# 22257_v8.net
KiCad netlist of a schematic drawn in EAGLE
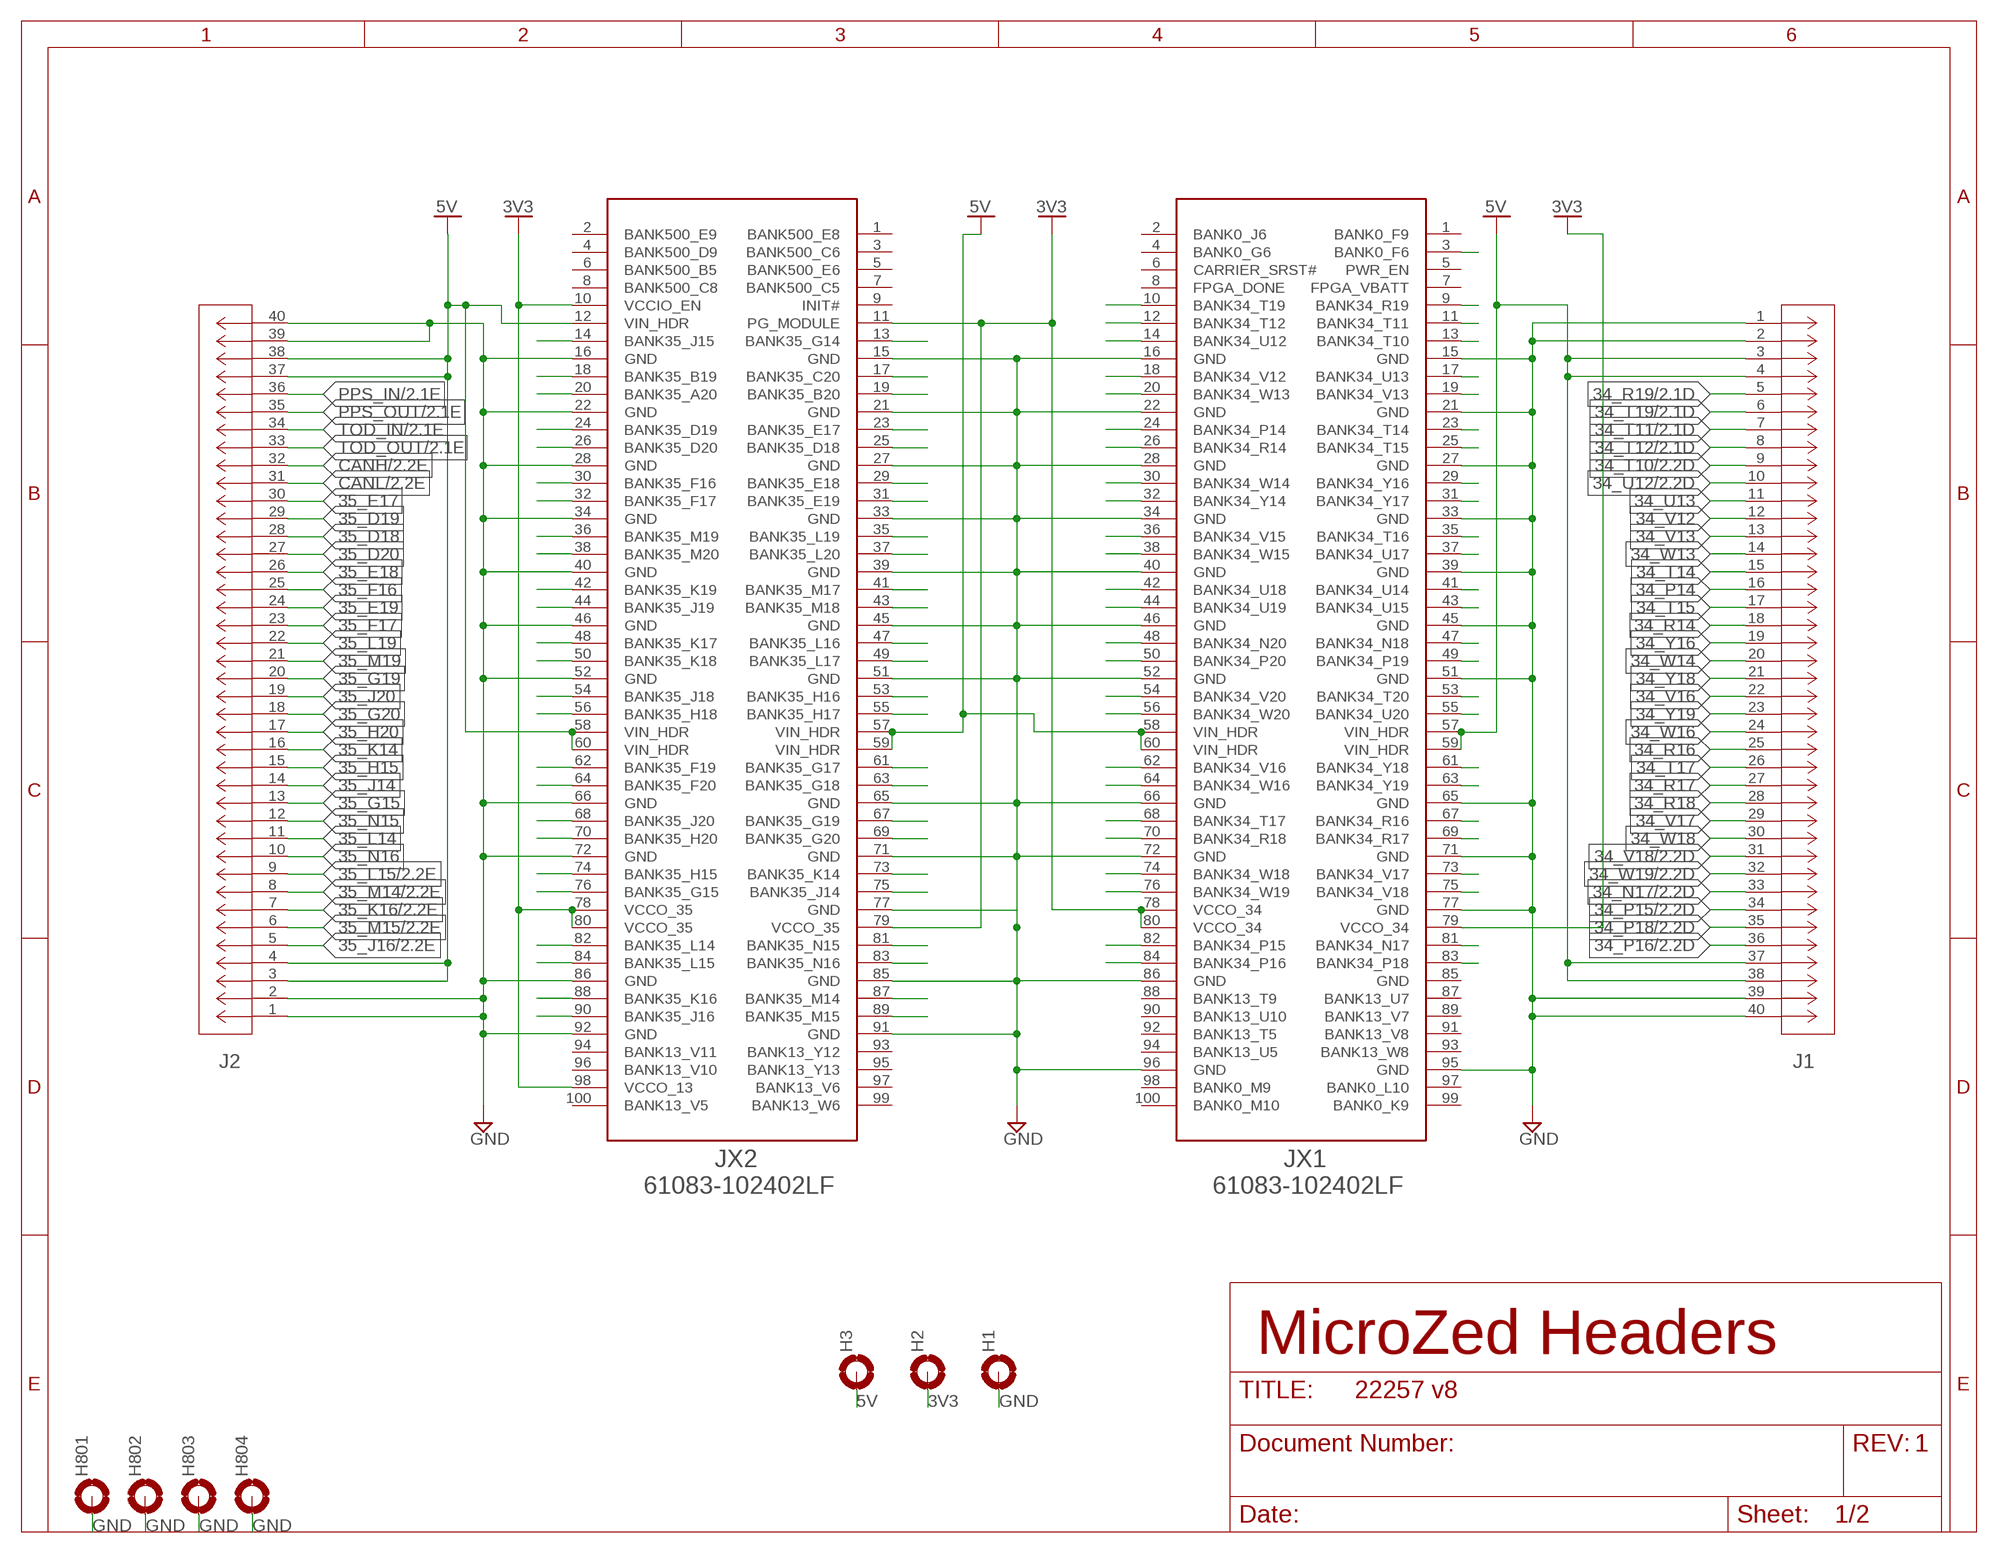
[diagram p0: schematic, sheet 1]
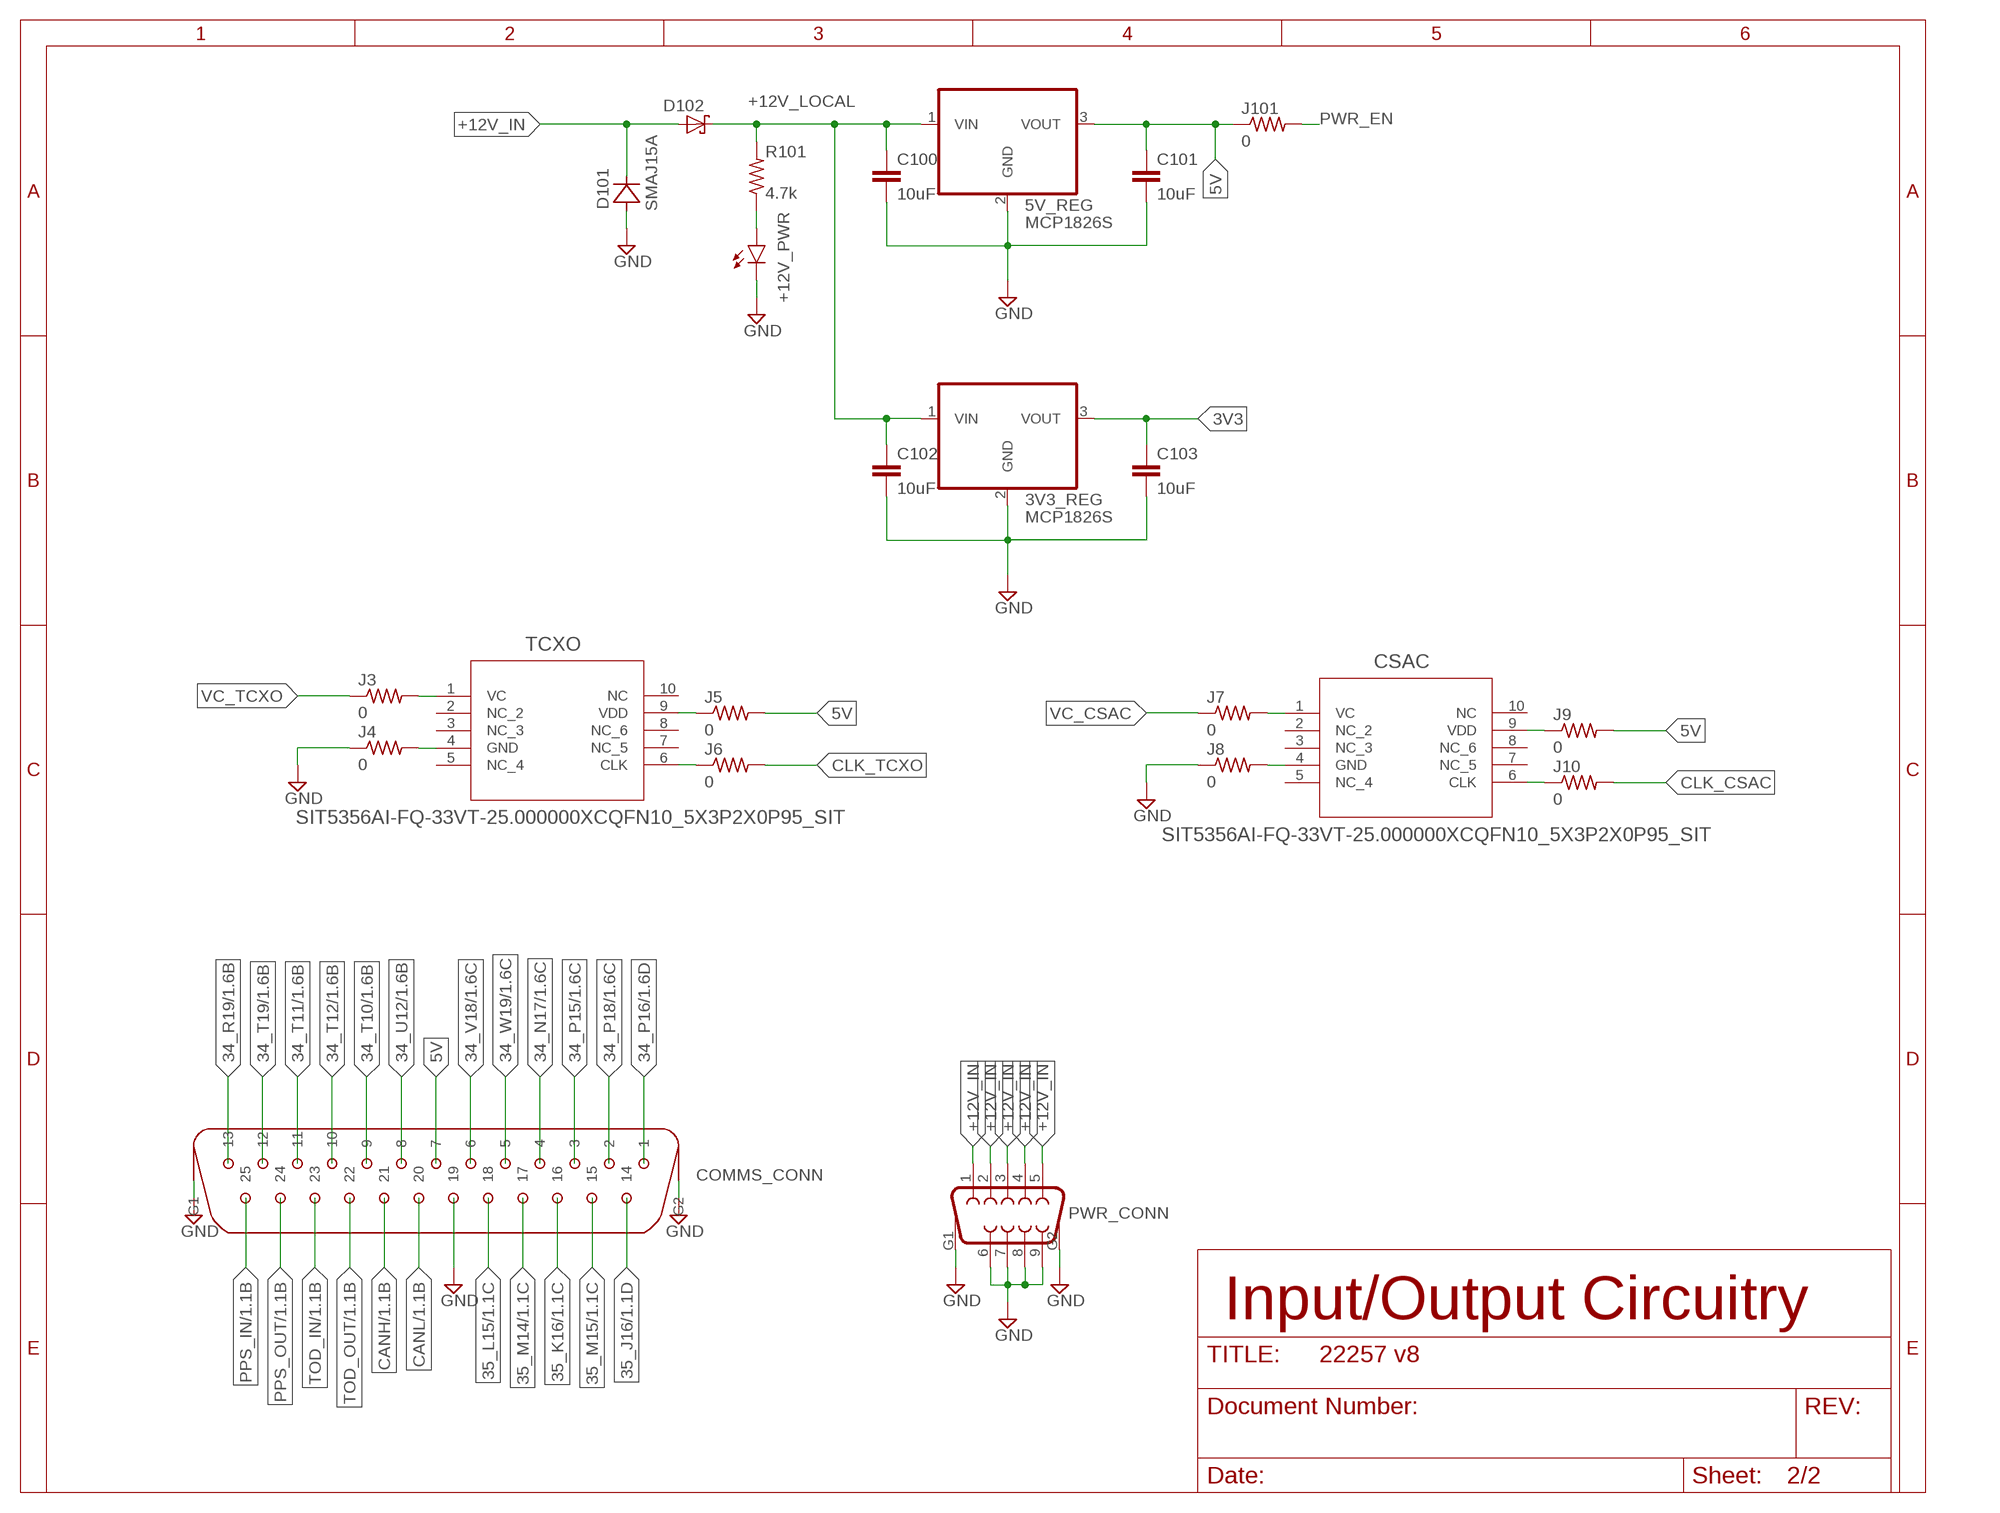
[diagram p1: schematic, sheet 2]

(export (version "E")
  (design (tool "Eeschema 10.0.6"))
  (components
    (comp (ref "H1")
      (value "MOUNT-PAD-ROUND5.0")
      (footprint "eagle-import:5,0-PAD")
      (libsource (lib "eagle-import") (part "MOUNT-PAD-ROUND5.0"))
    )
    (comp (ref "H2")
      (value "MOUNT-PAD-ROUND5.0")
      (footprint "eagle-import:5,0-PAD")
      (libsource (lib "eagle-import") (part "MOUNT-PAD-ROUND5.0"))
    )
    (comp (ref "H3")
      (value "MOUNT-PAD-ROUND5.0")
      (footprint "eagle-import:5,0-PAD")
      (libsource (lib "eagle-import") (part "MOUNT-PAD-ROUND5.0"))
    )
    (comp (ref "H801")
      (value "MOUNT-PAD-ROUND5.0")
      (footprint "eagle-import:5,0-PAD")
      (libsource (lib "eagle-import") (part "MOUNT-PAD-ROUND5.0"))
    )
    (comp (ref "H802")
      (value "MOUNT-PAD-ROUND5.0")
      (footprint "eagle-import:5,0-PAD")
      (libsource (lib "eagle-import") (part "MOUNT-PAD-ROUND5.0"))
    )
    (comp (ref "H803")
      (value "MOUNT-PAD-ROUND5.0")
      (footprint "eagle-import:5,0-PAD")
      (libsource (lib "eagle-import") (part "MOUNT-PAD-ROUND5.0"))
    )
    (comp (ref "H804")
      (value "MOUNT-PAD-ROUND5.0")
      (footprint "eagle-import:5,0-PAD")
      (libsource (lib "eagle-import") (part "MOUNT-PAD-ROUND5.0"))
    )
    (comp (ref "J1")
      (value "TD-120-G-AACON40_2X20_TU_HTS_SAI")
      (footprint "eagle-import:CON40_2X20_TU_HTS_SAI")
      (fields
        (field (name "MANUFACTURER_PART_NUMBER") "TD-120-G-AA")
        (field (name "COPYRIGHT") "Copyright (C) 2024 Ultra Librarian. All rights reserved.")
      )
      (libsource (lib "eagle-import") (part "TD-120-G-AACON40_2X20_TU_HTS_SAI"))
    )
    (comp (ref "J2")
      (value "TD-120-G-AACON40_2X20_TU_HTS_SAI")
      (footprint "eagle-import:CON40_2X20_TU_HTS_SAI")
      (fields
        (field (name "MANUFACTURER_PART_NUMBER") "TD-120-G-AA")
        (field (name "COPYRIGHT") "Copyright (C) 2024 Ultra Librarian. All rights reserved.")
      )
      (libsource (lib "eagle-import") (part "TD-120-G-AACON40_2X20_TU_HTS_SAI"))
    )
    (comp (ref "JX1")
      (value "61083-102402LF")
      (footprint "eagle-import:61083-102402LF")
      (libsource (lib "eagle-import") (part "61083-102402LF-JX1"))
    )
    (comp (ref "JX2")
      (value "61083-102402LF")
      (footprint "eagle-import:61083-102402LF")
      (libsource (lib "eagle-import") (part "61083-102402LF-JX2"))
    )
    (comp (ref "+12V_PWR")
      (value "LEDCHIP-LED0603")
      (footprint "eagle-import:CHIP-LED0603")
      (libsource (lib "eagle-import") (part "LEDCHIP-LED0603"))
    )
    (comp (ref "3V3_REG")
      (value "MCP1826S")
      (footprint "eagle-import:TO220-3")
      (libsource (lib "eagle-import") (part "MCP1826S"))
    )
    (comp (ref "5V_REG")
      (value "MCP1826S")
      (footprint "eagle-import:TO220-3")
      (libsource (lib "eagle-import") (part "MCP1826S"))
    )
    (comp (ref "C100")
      (value "10uF")
      (footprint "eagle-import:C0805")
      (libsource (lib "eagle-import") (part "C-EUC0805"))
    )
    (comp (ref "C101")
      (value "10uF")
      (footprint "eagle-import:C0805")
      (libsource (lib "eagle-import") (part "C-EUC0805"))
    )
    (comp (ref "C102")
      (value "10uF")
      (footprint "eagle-import:C0805")
      (libsource (lib "eagle-import") (part "C-EUC0805"))
    )
    (comp (ref "C103")
      (value "10uF")
      (footprint "eagle-import:C0805")
      (libsource (lib "eagle-import") (part "C-EUC0805"))
    )
    (comp (ref "COMMS_CONN")
      (value "M25HP")
      (footprint "eagle-import:M25HP")
      (libsource (lib "eagle-import") (part "M25HP"))
    )
    (comp (ref "CSAC")
      (value "SIT5356AI-FQ-33VT-25.000000XCQFN10_5X3P2X0P95_SIT")
      (footprint "eagle-import:CQFN10_5X3P2X0P95_SIT")
      (fields
        (field (name "MANUFACTURER_PART_NUMBER") "SIT5356AI-FQ-33VT-25.000000X")
        (field (name "COPYRIGHT") "Copyright (C) 2024 Ultra Librarian. All rights reserved.")
      )
      (libsource (lib "eagle-import") (part "SIT5356AI-FQ-33VT-25.000000XCQFN10_5X3P2X0P95_SIT"))
    )
    (comp (ref "D101")
      (value "SMAJ15A")
      (footprint "eagle-import:SMA")
      (libsource (lib "eagle-import") (part "MBRA340T3"))
    )
    (comp (ref "D102")
      (value "SCHOTTKY-DIODESMC")
      (footprint "eagle-import:SMC")
      (libsource (lib "eagle-import") (part "SCHOTTKY-DIODESMC"))
    )
    (comp (ref "J3")
      (value "0")
      (footprint "eagle-import:R0603")
      (libsource (lib "eagle-import") (part "R-US_R0603"))
    )
    (comp (ref "J4")
      (value "0")
      (footprint "eagle-import:R0603")
      (libsource (lib "eagle-import") (part "R-US_R0603"))
    )
    (comp (ref "J5")
      (value "0")
      (footprint "eagle-import:R0603")
      (libsource (lib "eagle-import") (part "R-US_R0603"))
    )
    (comp (ref "J6")
      (value "0")
      (footprint "eagle-import:R0603")
      (libsource (lib "eagle-import") (part "R-US_R0603"))
    )
    (comp (ref "J7")
      (value "0")
      (footprint "eagle-import:R0603")
      (libsource (lib "eagle-import") (part "R-US_R0603"))
    )
    (comp (ref "J8")
      (value "0")
      (footprint "eagle-import:R0603")
      (libsource (lib "eagle-import") (part "R-US_R0603"))
    )
    (comp (ref "J9")
      (value "0")
      (footprint "eagle-import:R0603")
      (libsource (lib "eagle-import") (part "R-US_R0603"))
    )
    (comp (ref "J10")
      (value "0")
      (footprint "eagle-import:R0603")
      (libsource (lib "eagle-import") (part "R-US_R0603"))
    )
    (comp (ref "J101")
      (value "0")
      (footprint "eagle-import:R0603")
      (libsource (lib "eagle-import") (part "R-US_R0603"))
    )
    (comp (ref "PWR_CONN")
      (value "DSUB9PIN")
      (footprint "eagle-import:DSUB9HP")
      (libsource (lib "eagle-import") (part "DSUB9PIN"))
    )
    (comp (ref "R101")
      (value "4.7k")
      (footprint "eagle-import:R0603")
      (libsource (lib "eagle-import") (part "R-US_R0603"))
    )
    (comp (ref "TCXO")
      (value "SIT5356AI-FQ-33VT-25.000000XCQFN10_5X3P2X0P95_SIT")
      (footprint "eagle-import:CQFN10_5X3P2X0P95_SIT")
      (fields
        (field (name "MANUFACTURER_PART_NUMBER") "SIT5356AI-FQ-33VT-25.000000X")
        (field (name "COPYRIGHT") "Copyright (C) 2024 Ultra Librarian. All rights reserved.")
      )
      (libsource (lib "eagle-import") (part "SIT5356AI-FQ-33VT-25.000000XCQFN10_5X3P2X0P95_SIT"))
    )
  )
  (nets
    (net (code "1") (name "+12V_IN") (class "Default")
      (node (ref "D101") (pin "C") (pinfunction "C_C") (pintype "passive"))
      (node (ref "D102") (pin "A") (pinfunction "A_A") (pintype "passive"))
      (node (ref "PWR_CONN") (pin "1") (pinfunction "1_1") (pintype "passive"))
      (node (ref "PWR_CONN") (pin "2") (pinfunction "2_2") (pintype "passive"))
      (node (ref "PWR_CONN") (pin "3") (pinfunction "3_3") (pintype "passive"))
      (node (ref "PWR_CONN") (pin "4") (pinfunction "4_4") (pintype "passive"))
      (node (ref "PWR_CONN") (pin "5") (pinfunction "5_5") (pintype "passive"))
    )
    (net (code "2") (name "+12V_LOCAL") (class "Default")
      (node (ref "3V3_REG") (pin "1") (pinfunction "VIN_1") (pintype "input"))
      (node (ref "5V_REG") (pin "1") (pinfunction "VIN_1") (pintype "input"))
      (node (ref "C100") (pin "1") (pinfunction "1_1") (pintype "passive"))
      (node (ref "C102") (pin "1") (pinfunction "1_1") (pintype "passive"))
      (node (ref "D102") (pin "C") (pinfunction "C_C") (pintype "passive"))
      (node (ref "R101") (pin "2") (pinfunction "2_2") (pintype "passive"))
    )
    (net (code "3") (name "3V3") (class "Default")
      (node (ref "3V3_REG") (pin "3") (pinfunction "VOUT_3") (pintype "passive"))
      (node (ref "C103") (pin "1") (pinfunction "1_1") (pintype "passive"))
      (node (ref "H2") (pin "B5") (pinfunction "MOUNT_B5") (pintype "passive"))
      (node (ref "JX1") (pin "78") (pinfunction "VCCO_34_78") (pintype "bidirectional"))
      (node (ref "JX1") (pin "79") (pinfunction "VCCO_34_79") (pintype "bidirectional"))
      (node (ref "JX1") (pin "80") (pinfunction "VCCO_34_80") (pintype "bidirectional"))
      (node (ref "JX2") (pin "10") (pinfunction "VCCIO_EN_10") (pintype "bidirectional"))
      (node (ref "JX2") (pin "11") (pinfunction "PG_MODULE_11") (pintype "bidirectional"))
      (node (ref "JX2") (pin "78") (pinfunction "VCCO_35_78") (pintype "bidirectional"))
      (node (ref "JX2") (pin "79") (pinfunction "VCCO_35_79") (pintype "bidirectional"))
      (node (ref "JX2") (pin "80") (pinfunction "VCCO_35_80") (pintype "bidirectional"))
      (node (ref "JX2") (pin "98") (pinfunction "VCCO_13_98") (pintype "bidirectional"))
    )
    (net (code "4") (name "5V") (class "Default")
      (node (ref "5V_REG") (pin "3") (pinfunction "VOUT_3") (pintype "passive"))
      (node (ref "C101") (pin "1") (pinfunction "1_1") (pintype "passive"))
      (node (ref "COMMS_CONN") (pin "7") (pinfunction "7_7") (pintype "bidirectional"))
      (node (ref "H3") (pin "B5") (pinfunction "MOUNT_B5") (pintype "passive"))
      (node (ref "J1") (pin "3") (pinfunction "3_3") (pintype "passive"))
      (node (ref "J1") (pin "37") (pinfunction "37_37") (pintype "passive"))
      (node (ref "J1") (pin "38") (pinfunction "38_38") (pintype "passive"))
      (node (ref "J1") (pin "4") (pinfunction "4_4") (pintype "passive"))
      (node (ref "J101") (pin "1") (pinfunction "1_1") (pintype "passive"))
      (node (ref "J2") (pin "3") (pinfunction "3_3") (pintype "passive"))
      (node (ref "J2") (pin "37") (pinfunction "37_37") (pintype "passive"))
      (node (ref "J2") (pin "38") (pinfunction "38_38") (pintype "passive"))
      (node (ref "J2") (pin "4") (pinfunction "4_4") (pintype "passive"))
      (node (ref "J5") (pin "2") (pinfunction "2_2") (pintype "passive"))
      (node (ref "J9") (pin "2") (pinfunction "2_2") (pintype "passive"))
      (node (ref "JX1") (pin "57") (pinfunction "VIN_HDR_57") (pintype "bidirectional"))
      (node (ref "JX1") (pin "58") (pinfunction "VIN_HDR_58") (pintype "bidirectional"))
      (node (ref "JX1") (pin "59") (pinfunction "VIN_HDR_59") (pintype "bidirectional"))
      (node (ref "JX1") (pin "60") (pinfunction "VIN_HDR_60") (pintype "bidirectional"))
      (node (ref "JX2") (pin "12") (pinfunction "VIN_HDR_12") (pintype "bidirectional"))
      (node (ref "JX2") (pin "57") (pinfunction "VIN_HDR_57") (pintype "bidirectional"))
      (node (ref "JX2") (pin "58") (pinfunction "VIN_HDR_58") (pintype "bidirectional"))
      (node (ref "JX2") (pin "59") (pinfunction "VIN_HDR_59") (pintype "bidirectional"))
      (node (ref "JX2") (pin "60") (pinfunction "VIN_HDR_60") (pintype "bidirectional"))
    )
    (net (code "5") (name "34_N17") (class "Default")
      (node (ref "COMMS_CONN") (pin "4") (pinfunction "4_4") (pintype "bidirectional"))
      (node (ref "J1") (pin "33") (pinfunction "33_33") (pintype "passive"))
      (node (ref "JX1") (pin "81") (pinfunction "BANK34_N17_81") (pintype "bidirectional"))
    )
    (net (code "6") (name "34_P14") (class "Default")
      (node (ref "J1") (pin "16") (pinfunction "16_16") (pintype "passive"))
      (node (ref "JX1") (pin "24") (pinfunction "BANK34_P14_24") (pintype "bidirectional"))
    )
    (net (code "7") (name "34_P15") (class "Default")
      (node (ref "COMMS_CONN") (pin "3") (pinfunction "3_3") (pintype "bidirectional"))
      (node (ref "J1") (pin "34") (pinfunction "34_34") (pintype "passive"))
      (node (ref "JX1") (pin "82") (pinfunction "BANK34_P15_82") (pintype "bidirectional"))
    )
    (net (code "8") (name "34_P16") (class "Default")
      (node (ref "COMMS_CONN") (pin "1") (pinfunction "1_1") (pintype "bidirectional"))
      (node (ref "J1") (pin "36") (pinfunction "36_36") (pintype "passive"))
      (node (ref "JX1") (pin "84") (pinfunction "BANK34_P16_84") (pintype "bidirectional"))
    )
    (net (code "9") (name "34_P18") (class "Default")
      (node (ref "COMMS_CONN") (pin "2") (pinfunction "2_2") (pintype "bidirectional"))
      (node (ref "J1") (pin "35") (pinfunction "35_35") (pintype "passive"))
      (node (ref "JX1") (pin "83") (pinfunction "BANK34_P18_83") (pintype "bidirectional"))
    )
    (net (code "10") (name "34_R14") (class "Default")
      (node (ref "J1") (pin "18") (pinfunction "18_18") (pintype "passive"))
      (node (ref "JX1") (pin "26") (pinfunction "BANK34_R14_26") (pintype "bidirectional"))
    )
    (net (code "11") (name "34_R16") (class "Default")
      (node (ref "J1") (pin "25") (pinfunction "25_25") (pintype "passive"))
      (node (ref "JX1") (pin "67") (pinfunction "BANK34_R16_67") (pintype "bidirectional"))
    )
    (net (code "12") (name "34_R17") (class "Default")
      (node (ref "J1") (pin "27") (pinfunction "27_27") (pintype "passive"))
      (node (ref "JX1") (pin "69") (pinfunction "BANK34_R17_69") (pintype "bidirectional"))
    )
    (net (code "13") (name "34_R18") (class "Default")
      (node (ref "J1") (pin "28") (pinfunction "28_28") (pintype "passive"))
      (node (ref "JX1") (pin "70") (pinfunction "BANK34_R18_70") (pintype "bidirectional"))
    )
    (net (code "14") (name "34_R19") (class "Default")
      (node (ref "COMMS_CONN") (pin "13") (pinfunction "13_13") (pintype "bidirectional"))
      (node (ref "J1") (pin "5") (pinfunction "5_5") (pintype "passive"))
      (node (ref "JX1") (pin "9") (pinfunction "BANK34_R19_9") (pintype "bidirectional"))
    )
    (net (code "15") (name "34_T10") (class "Default")
      (node (ref "COMMS_CONN") (pin "9") (pinfunction "9_9") (pintype "bidirectional"))
      (node (ref "J1") (pin "9") (pinfunction "9_9") (pintype "passive"))
      (node (ref "JX1") (pin "13") (pinfunction "BANK34_T10_13") (pintype "bidirectional"))
    )
    (net (code "16") (name "34_T11") (class "Default")
      (node (ref "COMMS_CONN") (pin "11") (pinfunction "11_11") (pintype "bidirectional"))
      (node (ref "J1") (pin "7") (pinfunction "7_7") (pintype "passive"))
      (node (ref "JX1") (pin "11") (pinfunction "BANK34_T11_11") (pintype "bidirectional"))
    )
    (net (code "17") (name "34_T12") (class "Default")
      (node (ref "COMMS_CONN") (pin "10") (pinfunction "10_10") (pintype "bidirectional"))
      (node (ref "J1") (pin "8") (pinfunction "8_8") (pintype "passive"))
      (node (ref "JX1") (pin "12") (pinfunction "BANK34_T12_12") (pintype "bidirectional"))
    )
    (net (code "18") (name "34_T14") (class "Default")
      (node (ref "J1") (pin "15") (pinfunction "15_15") (pintype "passive"))
      (node (ref "JX1") (pin "23") (pinfunction "BANK34_T14_23") (pintype "bidirectional"))
    )
    (net (code "19") (name "34_T15") (class "Default")
      (node (ref "J1") (pin "17") (pinfunction "17_17") (pintype "passive"))
      (node (ref "JX1") (pin "25") (pinfunction "BANK34_T15_25") (pintype "bidirectional"))
    )
    (net (code "20") (name "34_T17") (class "Default")
      (node (ref "J1") (pin "26") (pinfunction "26_26") (pintype "passive"))
      (node (ref "JX1") (pin "68") (pinfunction "BANK34_T17_68") (pintype "bidirectional"))
    )
    (net (code "21") (name "34_T19") (class "Default")
      (node (ref "COMMS_CONN") (pin "12") (pinfunction "12_12") (pintype "bidirectional"))
      (node (ref "J1") (pin "6") (pinfunction "6_6") (pintype "passive"))
      (node (ref "JX1") (pin "10") (pinfunction "BANK34_T19_10") (pintype "bidirectional"))
    )
    (net (code "22") (name "34_U12") (class "Default")
      (node (ref "COMMS_CONN") (pin "8") (pinfunction "8_8") (pintype "bidirectional"))
      (node (ref "J1") (pin "10") (pinfunction "10_10") (pintype "passive"))
      (node (ref "JX1") (pin "14") (pinfunction "BANK34_U12_14") (pintype "bidirectional"))
    )
    (net (code "23") (name "34_U13") (class "Default")
      (node (ref "J1") (pin "11") (pinfunction "11_11") (pintype "passive"))
      (node (ref "JX1") (pin "17") (pinfunction "BANK34_U13_17") (pintype "bidirectional"))
    )
    (net (code "24") (name "34_V12") (class "Default")
      (node (ref "J1") (pin "12") (pinfunction "12_12") (pintype "passive"))
      (node (ref "JX1") (pin "18") (pinfunction "BANK34_V12_18") (pintype "bidirectional"))
    )
    (net (code "25") (name "34_V13") (class "Default")
      (node (ref "J1") (pin "13") (pinfunction "13_13") (pintype "passive"))
      (node (ref "JX1") (pin "19") (pinfunction "BANK34_V13_19") (pintype "bidirectional"))
    )
    (net (code "26") (name "34_V16") (class "Default")
      (node (ref "J1") (pin "22") (pinfunction "22_22") (pintype "passive"))
      (node (ref "JX1") (pin "62") (pinfunction "BANK34_V16_62") (pintype "bidirectional"))
    )
    (net (code "27") (name "34_V17") (class "Default")
      (node (ref "J1") (pin "29") (pinfunction "29_29") (pintype "passive"))
      (node (ref "JX1") (pin "73") (pinfunction "BANK34_V17_73") (pintype "bidirectional"))
    )
    (net (code "28") (name "34_V18") (class "Default")
      (node (ref "COMMS_CONN") (pin "6") (pinfunction "6_6") (pintype "bidirectional"))
      (node (ref "J1") (pin "31") (pinfunction "31_31") (pintype "passive"))
      (node (ref "JX1") (pin "75") (pinfunction "BANK34_V18_75") (pintype "bidirectional"))
    )
    (net (code "29") (name "34_W13") (class "Default")
      (node (ref "J1") (pin "14") (pinfunction "14_14") (pintype "passive"))
      (node (ref "JX1") (pin "20") (pinfunction "BANK34_W13_20") (pintype "bidirectional"))
    )
    (net (code "30") (name "34_W14") (class "Default")
      (node (ref "J1") (pin "20") (pinfunction "20_20") (pintype "passive"))
      (node (ref "JX1") (pin "30") (pinfunction "BANK34_W14_30") (pintype "bidirectional"))
    )
    (net (code "31") (name "34_W16") (class "Default")
      (node (ref "J1") (pin "24") (pinfunction "24_24") (pintype "passive"))
      (node (ref "JX1") (pin "64") (pinfunction "BANK34_W16_64") (pintype "bidirectional"))
    )
    (net (code "32") (name "34_W18") (class "Default")
      (node (ref "J1") (pin "30") (pinfunction "30_30") (pintype "passive"))
      (node (ref "JX1") (pin "74") (pinfunction "BANK34_W18_74") (pintype "bidirectional"))
    )
    (net (code "33") (name "34_W19") (class "Default")
      (node (ref "COMMS_CONN") (pin "5") (pinfunction "5_5") (pintype "bidirectional"))
      (node (ref "J1") (pin "32") (pinfunction "32_32") (pintype "passive"))
      (node (ref "JX1") (pin "76") (pinfunction "BANK34_W19_76") (pintype "bidirectional"))
    )
    (net (code "34") (name "34_Y16") (class "Default")
      (node (ref "J1") (pin "19") (pinfunction "19_19") (pintype "passive"))
      (node (ref "JX1") (pin "29") (pinfunction "BANK34_Y16_29") (pintype "bidirectional"))
    )
    (net (code "35") (name "34_Y18") (class "Default")
      (node (ref "J1") (pin "21") (pinfunction "21_21") (pintype "passive"))
      (node (ref "JX1") (pin "61") (pinfunction "BANK34_Y18_61") (pintype "bidirectional"))
    )
    (net (code "36") (name "34_Y19") (class "Default")
      (node (ref "J1") (pin "23") (pinfunction "23_23") (pintype "passive"))
      (node (ref "JX1") (pin "63") (pinfunction "BANK34_Y19_63") (pintype "bidirectional"))
    )
    (net (code "37") (name "35_D18") (class "Default")
      (node (ref "J2") (pin "28") (pinfunction "28_28") (pintype "passive"))
      (node (ref "JX2") (pin "25") (pinfunction "BANK35_D18_25") (pintype "bidirectional"))
    )
    (net (code "38") (name "35_D19") (class "Default")
      (node (ref "J2") (pin "29") (pinfunction "29_29") (pintype "passive"))
      (node (ref "JX2") (pin "24") (pinfunction "BANK35_D19_24") (pintype "bidirectional"))
    )
    (net (code "39") (name "35_D20") (class "Default")
      (node (ref "J2") (pin "27") (pinfunction "27_27") (pintype "passive"))
      (node (ref "JX2") (pin "26") (pinfunction "BANK35_D20_26") (pintype "bidirectional"))
    )
    (net (code "40") (name "35_E17") (class "Default")
      (node (ref "J2") (pin "30") (pinfunction "30_30") (pintype "passive"))
      (node (ref "JX2") (pin "23") (pinfunction "BANK35_E17_23") (pintype "bidirectional"))
    )
    (net (code "41") (name "35_E18") (class "Default")
      (node (ref "J2") (pin "26") (pinfunction "26_26") (pintype "passive"))
      (node (ref "JX2") (pin "29") (pinfunction "BANK35_E18_29") (pintype "bidirectional"))
    )
    (net (code "42") (name "35_E19") (class "Default")
      (node (ref "J2") (pin "24") (pinfunction "24_24") (pintype "passive"))
      (node (ref "JX2") (pin "31") (pinfunction "BANK35_E19_31") (pintype "bidirectional"))
    )
    (net (code "43") (name "35_F16") (class "Default")
      (node (ref "J2") (pin "25") (pinfunction "25_25") (pintype "passive"))
      (node (ref "JX2") (pin "30") (pinfunction "BANK35_F16_30") (pintype "bidirectional"))
    )
    (net (code "44") (name "35_F17") (class "Default")
      (node (ref "J2") (pin "23") (pinfunction "23_23") (pintype "passive"))
      (node (ref "JX2") (pin "32") (pinfunction "BANK35_F17_32") (pintype "bidirectional"))
    )
    (net (code "45") (name "35_G15") (class "Default")
      (node (ref "J2") (pin "13") (pinfunction "13_13") (pintype "passive"))
      (node (ref "JX2") (pin "76") (pinfunction "BANK35_G15_76") (pintype "bidirectional"))
    )
    (net (code "46") (name "35_G19") (class "Default")
      (node (ref "J2") (pin "20") (pinfunction "20_20") (pintype "passive"))
      (node (ref "JX2") (pin "67") (pinfunction "BANK35_G19_67") (pintype "bidirectional"))
    )
    (net (code "47") (name "35_G20") (class "Default")
      (node (ref "J2") (pin "18") (pinfunction "18_18") (pintype "passive"))
      (node (ref "JX2") (pin "69") (pinfunction "BANK35_G20_69") (pintype "bidirectional"))
    )
    (net (code "48") (name "35_H15") (class "Default")
      (node (ref "J2") (pin "15") (pinfunction "15_15") (pintype "passive"))
      (node (ref "JX2") (pin "74") (pinfunction "BANK35_H15_74") (pintype "bidirectional"))
    )
    (net (code "49") (name "35_H20") (class "Default")
      (node (ref "J2") (pin "17") (pinfunction "17_17") (pintype "passive"))
      (node (ref "JX2") (pin "70") (pinfunction "BANK35_H20_70") (pintype "bidirectional"))
    )
    (net (code "50") (name "35_J14") (class "Default")
      (node (ref "J2") (pin "14") (pinfunction "14_14") (pintype "passive"))
      (node (ref "JX2") (pin "75") (pinfunction "BANK35_J14_75") (pintype "bidirectional"))
    )
    (net (code "51") (name "35_J16") (class "Default")
      (node (ref "COMMS_CONN") (pin "14") (pinfunction "14_14") (pintype "bidirectional"))
      (node (ref "J2") (pin "5") (pinfunction "5_5") (pintype "passive"))
      (node (ref "JX2") (pin "90") (pinfunction "BANK35_J16_90") (pintype "bidirectional"))
    )
    (net (code "52") (name "35_J20") (class "Default")
      (node (ref "J2") (pin "19") (pinfunction "19_19") (pintype "passive"))
      (node (ref "JX2") (pin "68") (pinfunction "BANK35_J20_68") (pintype "bidirectional"))
    )
    (net (code "53") (name "35_K14") (class "Default")
      (node (ref "J2") (pin "16") (pinfunction "16_16") (pintype "passive"))
      (node (ref "JX2") (pin "73") (pinfunction "BANK35_K14_73") (pintype "bidirectional"))
    )
    (net (code "54") (name "35_K16") (class "Default")
      (node (ref "COMMS_CONN") (pin "16") (pinfunction "16_16") (pintype "bidirectional"))
      (node (ref "J2") (pin "7") (pinfunction "7_7") (pintype "passive"))
      (node (ref "JX2") (pin "88") (pinfunction "BANK35_K16_88") (pintype "bidirectional"))
    )
    (net (code "55") (name "35_L14") (class "Default")
      (node (ref "J2") (pin "11") (pinfunction "11_11") (pintype "passive"))
      (node (ref "JX2") (pin "82") (pinfunction "BANK35_L14_82") (pintype "bidirectional"))
    )
    (net (code "56") (name "35_L15") (class "Default")
      (node (ref "COMMS_CONN") (pin "18") (pinfunction "18_18") (pintype "bidirectional"))
      (node (ref "J2") (pin "9") (pinfunction "9_9") (pintype "passive"))
      (node (ref "JX2") (pin "84") (pinfunction "BANK35_L15_84") (pintype "bidirectional"))
    )
    (net (code "57") (name "35_L19") (class "Default")
      (node (ref "J2") (pin "22") (pinfunction "22_22") (pintype "passive"))
      (node (ref "JX2") (pin "35") (pinfunction "BANK35_L19_35") (pintype "bidirectional"))
    )
    (net (code "58") (name "35_M14") (class "Default")
      (node (ref "COMMS_CONN") (pin "17") (pinfunction "17_17") (pintype "bidirectional"))
      (node (ref "J2") (pin "8") (pinfunction "8_8") (pintype "passive"))
      (node (ref "JX2") (pin "87") (pinfunction "BANK35_M14_87") (pintype "bidirectional"))
    )
    (net (code "59") (name "35_M15") (class "Default")
      (node (ref "COMMS_CONN") (pin "15") (pinfunction "15_15") (pintype "bidirectional"))
      (node (ref "J2") (pin "6") (pinfunction "6_6") (pintype "passive"))
      (node (ref "JX2") (pin "89") (pinfunction "BANK35_M15_89") (pintype "bidirectional"))
    )
    (net (code "60") (name "35_M19") (class "Default")
      (node (ref "J2") (pin "21") (pinfunction "21_21") (pintype "passive"))
      (node (ref "JX2") (pin "36") (pinfunction "BANK35_M19_36") (pintype "bidirectional"))
    )
    (net (code "61") (name "35_N15") (class "Default")
      (node (ref "J2") (pin "12") (pinfunction "12_12") (pintype "passive"))
      (node (ref "JX2") (pin "81") (pinfunction "BANK35_N15_81") (pintype "bidirectional"))
    )
    (net (code "62") (name "35_N16") (class "Default")
      (node (ref "J2") (pin "10") (pinfunction "10_10") (pintype "passive"))
      (node (ref "JX2") (pin "83") (pinfunction "BANK35_N16_83") (pintype "bidirectional"))
    )
    (net (code "63") (name "CANH") (class "Default")
      (node (ref "COMMS_CONN") (pin "21") (pinfunction "21_21") (pintype "bidirectional"))
      (node (ref "J2") (pin "32") (pinfunction "32_32") (pintype "passive"))
    )
    (net (code "64") (name "CANL") (class "Default")
      (node (ref "COMMS_CONN") (pin "20") (pinfunction "20_20") (pintype "bidirectional"))
      (node (ref "J2") (pin "31") (pinfunction "31_31") (pintype "passive"))
    )
    (net (code "65") (name "CLK_CSAC") (class "Default")
      (node (ref "J10") (pin "2") (pinfunction "2_2") (pintype "passive"))
    )
    (net (code "66") (name "CLK_TCXO") (class "Default")
      (node (ref "J6") (pin "2") (pinfunction "2_2") (pintype "passive"))
    )
    (net (code "67") (name "GND") (class "Default")
      (node (ref "+12V_PWR") (pin "C") (pinfunction "C_C") (pintype "passive"))
      (node (ref "3V3_REG") (pin "2") (pinfunction "GND_2") (pintype "input"))
      (node (ref "5V_REG") (pin "2") (pinfunction "GND_2") (pintype "input"))
      (node (ref "C100") (pin "2") (pinfunction "2_2") (pintype "passive"))
      (node (ref "C101") (pin "2") (pinfunction "2_2") (pintype "passive"))
      (node (ref "C102") (pin "2") (pinfunction "2_2") (pintype "passive"))
      (node (ref "C103") (pin "2") (pinfunction "2_2") (pintype "passive"))
      (node (ref "COMMS_CONN") (pin "19") (pinfunction "19_19") (pintype "bidirectional"))
      (node (ref "COMMS_CONN") (pin "G1") (pinfunction "G1_G1") (pintype "bidirectional"))
      (node (ref "COMMS_CONN") (pin "G2") (pinfunction "G2_G2") (pintype "bidirectional"))
      (node (ref "D101") (pin "A") (pinfunction "A_A") (pintype "passive"))
      (node (ref "H1") (pin "B5") (pinfunction "MOUNT_B5") (pintype "passive"))
      (node (ref "H801") (pin "B5") (pinfunction "MOUNT_B5") (pintype "passive"))
      (node (ref "H802") (pin "B5") (pinfunction "MOUNT_B5") (pintype "passive"))
      (node (ref "H803") (pin "B5") (pinfunction "MOUNT_B5") (pintype "passive"))
      (node (ref "H804") (pin "B5") (pinfunction "MOUNT_B5") (pintype "passive"))
      (node (ref "J1") (pin "1") (pinfunction "1_1") (pintype "passive"))
      (node (ref "J1") (pin "2") (pinfunction "2_2") (pintype "passive"))
      (node (ref "J1") (pin "39") (pinfunction "39_39") (pintype "passive"))
      (node (ref "J1") (pin "40") (pinfunction "40_40") (pintype "passive"))
      (node (ref "J2") (pin "1") (pinfunction "1_1") (pintype "passive"))
      (node (ref "J2") (pin "2") (pinfunction "2_2") (pintype "passive"))
      (node (ref "J2") (pin "39") (pinfunction "39_39") (pintype "passive"))
      (node (ref "J2") (pin "40") (pinfunction "40_40") (pintype "passive"))
      (node (ref "J4") (pin "1") (pinfunction "1_1") (pintype "passive"))
      (node (ref "J8") (pin "1") (pinfunction "1_1") (pintype "passive"))
      (node (ref "JX1") (pin "15") (pinfunction "GND_15") (pintype "bidirectional"))
      (node (ref "JX1") (pin "16") (pinfunction "GND_16") (pintype "bidirectional"))
      (node (ref "JX1") (pin "21") (pinfunction "GND_21") (pintype "bidirectional"))
      (node (ref "JX1") (pin "22") (pinfunction "GND_22") (pintype "bidirectional"))
      (node (ref "JX1") (pin "27") (pinfunction "GND_27") (pintype "bidirectional"))
      (node (ref "JX1") (pin "28") (pinfunction "GND_28") (pintype "bidirectional"))
      (node (ref "JX1") (pin "33") (pinfunction "GND_33") (pintype "bidirectional"))
      (node (ref "JX1") (pin "34") (pinfunction "GND_34") (pintype "bidirectional"))
      (node (ref "JX1") (pin "39") (pinfunction "GND_39") (pintype "bidirectional"))
      (node (ref "JX1") (pin "40") (pinfunction "GND_40") (pintype "bidirectional"))
      (node (ref "JX1") (pin "45") (pinfunction "GND_45") (pintype "bidirectional"))
      (node (ref "JX1") (pin "46") (pinfunction "GND_46") (pintype "bidirectional"))
      (node (ref "JX1") (pin "51") (pinfunction "GND_51") (pintype "bidirectional"))
      (node (ref "JX1") (pin "52") (pinfunction "GND_52") (pintype "bidirectional"))
      (node (ref "JX1") (pin "65") (pinfunction "GND_65") (pintype "bidirectional"))
      (node (ref "JX1") (pin "66") (pinfunction "GND_66") (pintype "bidirectional"))
      (node (ref "JX1") (pin "71") (pinfunction "GND_71") (pintype "bidirectional"))
      (node (ref "JX1") (pin "72") (pinfunction "GND_72") (pintype "bidirectional"))
      (node (ref "JX1") (pin "77") (pinfunction "GND_77") (pintype "bidirectional"))
      (node (ref "JX1") (pin "86") (pinfunction "GND_86") (pintype "bidirectional"))
      (node (ref "JX1") (pin "95") (pinfunction "GND_95") (pintype "bidirectional"))
      (node (ref "JX1") (pin "96") (pinfunction "GND_96") (pintype "bidirectional"))
      (node (ref "JX2") (pin "15") (pinfunction "GND_15") (pintype "bidirectional"))
      (node (ref "JX2") (pin "16") (pinfunction "GND_16") (pintype "bidirectional"))
      (node (ref "JX2") (pin "21") (pinfunction "GND_21") (pintype "bidirectional"))
      (node (ref "JX2") (pin "22") (pinfunction "GND_22") (pintype "bidirectional"))
      (node (ref "JX2") (pin "27") (pinfunction "GND_27") (pintype "bidirectional"))
      (node (ref "JX2") (pin "28") (pinfunction "GND_28") (pintype "bidirectional"))
      (node (ref "JX2") (pin "33") (pinfunction "GND_33") (pintype "bidirectional"))
      (node (ref "JX2") (pin "34") (pinfunction "GND_34") (pintype "bidirectional"))
      (node (ref "JX2") (pin "39") (pinfunction "GND_39") (pintype "bidirectional"))
      (node (ref "JX2") (pin "40") (pinfunction "GND_40") (pintype "bidirectional"))
      (node (ref "JX2") (pin "45") (pinfunction "GND_45") (pintype "bidirectional"))
      (node (ref "JX2") (pin "46") (pinfunction "GND_46") (pintype "bidirectional"))
      (node (ref "JX2") (pin "51") (pinfunction "GND_51") (pintype "bidirectional"))
      (node (ref "JX2") (pin "52") (pinfunction "GND_52") (pintype "bidirectional"))
      (node (ref "JX2") (pin "65") (pinfunction "GND_65") (pintype "bidirectional"))
      (node (ref "JX2") (pin "66") (pinfunction "GND_66") (pintype "bidirectional"))
      (node (ref "JX2") (pin "71") (pinfunction "GND_71") (pintype "bidirectional"))
      (node (ref "JX2") (pin "72") (pinfunction "GND_72") (pintype "bidirectional"))
      (node (ref "JX2") (pin "77") (pinfunction "GND_77") (pintype "bidirectional"))
      (node (ref "JX2") (pin "85") (pinfunction "GND_85") (pintype "bidirectional"))
      (node (ref "JX2") (pin "86") (pinfunction "GND_86") (pintype "bidirectional"))
      (node (ref "JX2") (pin "91") (pinfunction "GND_91") (pintype "bidirectional"))
      (node (ref "JX2") (pin "92") (pinfunction "GND_92") (pintype "bidirectional"))
      (node (ref "PWR_CONN") (pin "6") (pinfunction "6_6") (pintype "passive"))
      (node (ref "PWR_CONN") (pin "7") (pinfunction "7_7") (pintype "passive"))
      (node (ref "PWR_CONN") (pin "8") (pinfunction "8_8") (pintype "passive"))
      (node (ref "PWR_CONN") (pin "9") (pinfunction "9_9") (pintype "passive"))
      (node (ref "PWR_CONN") (pin "G1") (pinfunction "10_G1") (pintype "passive"))
      (node (ref "PWR_CONN") (pin "G2") (pinfunction "11_G2") (pintype "passive"))
    )
    (net (code "68") (name "Net-(+12V_PWR-PadA)") (class "Default")
      (node (ref "+12V_PWR") (pin "A") (pinfunction "A_A") (pintype "passive"))
      (node (ref "R101") (pin "1") (pinfunction "1_1") (pintype "passive"))
    )
    (net (code "69") (name "Net-(CSAC-CLK)") (class "Default")
      (node (ref "CSAC") (pin "6") (pinfunction "CLK_6") (pintype "output"))
      (node (ref "J10") (pin "1") (pinfunction "1_1") (pintype "passive"))
    )
    (net (code "70") (name "Net-(CSAC-GND)") (class "Default")
      (node (ref "CSAC") (pin "4") (pinfunction "GND_4") (pintype "passive"))
      (node (ref "J8") (pin "2") (pinfunction "2_2") (pintype "passive"))
    )
    (net (code "71") (name "Net-(CSAC-VC)") (class "Default")
      (node (ref "CSAC") (pin "1") (pinfunction "VC_1") (pintype "input"))
      (node (ref "J7") (pin "2") (pinfunction "2_2") (pintype "passive"))
    )
    (net (code "72") (name "Net-(CSAC-VDD)") (class "Default")
      (node (ref "CSAC") (pin "9") (pinfunction "VDD_9") (pintype "power_in"))
      (node (ref "J9") (pin "1") (pinfunction "1_1") (pintype "passive"))
    )
    (net (code "73") (name "Net-(TCXO-CLK)") (class "Default")
      (node (ref "J6") (pin "1") (pinfunction "1_1") (pintype "passive"))
      (node (ref "TCXO") (pin "6") (pinfunction "CLK_6") (pintype "output"))
    )
    (net (code "74") (name "Net-(TCXO-GND)") (class "Default")
      (node (ref "J4") (pin "2") (pinfunction "2_2") (pintype "passive"))
      (node (ref "TCXO") (pin "4") (pinfunction "GND_4") (pintype "passive"))
    )
    (net (code "75") (name "Net-(TCXO-VC)") (class "Default")
      (node (ref "J3") (pin "2") (pinfunction "2_2") (pintype "passive"))
      (node (ref "TCXO") (pin "1") (pinfunction "VC_1") (pintype "input"))
    )
    (net (code "76") (name "Net-(TCXO-VDD)") (class "Default")
      (node (ref "J5") (pin "1") (pinfunction "1_1") (pintype "passive"))
      (node (ref "TCXO") (pin "9") (pinfunction "VDD_9") (pintype "power_in"))
    )
    (net (code "77") (name "PPS_IN") (class "Default")
      (node (ref "COMMS_CONN") (pin "25") (pinfunction "25_25") (pintype "bidirectional"))
      (node (ref "J2") (pin "36") (pinfunction "36_36") (pintype "passive"))
    )
    (net (code "78") (name "PPS_OUT") (class "Default")
      (node (ref "COMMS_CONN") (pin "24") (pinfunction "24_24") (pintype "bidirectional"))
      (node (ref "J2") (pin "35") (pinfunction "35_35") (pintype "passive"))
    )
    (net (code "79") (name "PWR_EN") (class "Default")
      (node (ref "J101") (pin "2") (pinfunction "2_2") (pintype "passive"))
      (node (ref "JX1") (pin "3") (pinfunction "BANK0_F6_3") (pintype "bidirectional"))
    )
    (net (code "80") (name "TOD_IN") (class "Default")
      (node (ref "COMMS_CONN") (pin "23") (pinfunction "23_23") (pintype "bidirectional"))
      (node (ref "J2") (pin "34") (pinfunction "34_34") (pintype "passive"))
    )
    (net (code "81") (name "TOD_OUT") (class "Default")
      (node (ref "COMMS_CONN") (pin "22") (pinfunction "22_22") (pintype "bidirectional"))
      (node (ref "J2") (pin "33") (pinfunction "33_33") (pintype "passive"))
    )
    (net (code "82") (name "VC_CSAC") (class "Default")
      (node (ref "J7") (pin "1") (pinfunction "1_1") (pintype "passive"))
    )
    (net (code "83") (name "VC_TCXO") (class "Default")
      (node (ref "J3") (pin "1") (pinfunction "1_1") (pintype "passive"))
    )
    (net (code "84") (name "unconnected-(CSAC-NC-Pad10)") (class "Default")
      (node (ref "CSAC") (pin "10") (pinfunction "NC_10") (pintype "no_connect"))
    )
    (net (code "85") (name "unconnected-(CSAC-NC_2-Pad2)") (class "Default")
      (node (ref "CSAC") (pin "2") (pinfunction "NC_2_2") (pintype "no_connect"))
    )
    (net (code "86") (name "unconnected-(CSAC-NC_3-Pad3)") (class "Default")
      (node (ref "CSAC") (pin "3") (pinfunction "NC_3_3") (pintype "no_connect"))
    )
    (net (code "87") (name "unconnected-(CSAC-NC_4-Pad5)") (class "Default")
      (node (ref "CSAC") (pin "5") (pinfunction "NC_4_5") (pintype "no_connect"))
    )
    (net (code "88") (name "unconnected-(CSAC-NC_5-Pad7)") (class "Default")
      (node (ref "CSAC") (pin "7") (pinfunction "NC_5_7") (pintype "no_connect"))
    )
    (net (code "89") (name "unconnected-(CSAC-NC_6-Pad8)") (class "Default")
      (node (ref "CSAC") (pin "8") (pinfunction "NC_6_8") (pintype "no_connect"))
    )
    (net (code "90") (name "unconnected-(JX1-BANK0_F9-Pad1)") (class "Default")
      (node (ref "JX1") (pin "1") (pinfunction "BANK0_F9_1") (pintype "bidirectional"))
    )
    (net (code "91") (name "unconnected-(JX1-BANK0_G6-Pad4)") (class "Default")
      (node (ref "JX1") (pin "4") (pinfunction "BANK0_G6_4") (pintype "bidirectional"))
    )
    (net (code "92") (name "unconnected-(JX1-BANK0_J6-Pad2)") (class "Default")
      (node (ref "JX1") (pin "2") (pinfunction "BANK0_J6_2") (pintype "bidirectional"))
    )
    (net (code "93") (name "unconnected-(JX1-BANK0_K9-Pad99)") (class "Default")
      (node (ref "JX1") (pin "99") (pinfunction "BANK0_K9_99") (pintype "bidirectional"))
    )
    (net (code "94") (name "unconnected-(JX1-BANK0_L10-Pad97)") (class "Default")
      (node (ref "JX1") (pin "97") (pinfunction "BANK0_L10_97") (pintype "bidirectional"))
    )
    (net (code "95") (name "unconnected-(JX1-BANK0_M9-Pad98)") (class "Default")
      (node (ref "JX1") (pin "98") (pinfunction "BANK0_M9_98") (pintype "bidirectional"))
    )
    (net (code "96") (name "unconnected-(JX1-BANK0_M10-Pad100)") (class "Default")
      (node (ref "JX1") (pin "100") (pinfunction "BANK0_M10_100") (pintype "bidirectional"))
    )
    (net (code "97") (name "unconnected-(JX1-BANK13_T5-Pad92)") (class "Default")
      (node (ref "JX1") (pin "92") (pinfunction "BANK13_T5_92") (pintype "bidirectional"))
    )
    (net (code "98") (name "unconnected-(JX1-BANK13_T9-Pad88)") (class "Default")
      (node (ref "JX1") (pin "88") (pinfunction "BANK13_T9_88") (pintype "bidirectional"))
    )
    (net (code "99") (name "unconnected-(JX1-BANK13_U5-Pad94)") (class "Default")
      (node (ref "JX1") (pin "94") (pinfunction "BANK13_U5_94") (pintype "bidirectional"))
    )
    (net (code "100") (name "unconnected-(JX1-BANK13_U7-Pad87)") (class "Default")
      (node (ref "JX1") (pin "87") (pinfunction "BANK13_U7_87") (pintype "bidirectional"))
    )
    (net (code "101") (name "unconnected-(JX1-BANK13_U10-Pad90)") (class "Default")
      (node (ref "JX1") (pin "90") (pinfunction "BANK13_U10_90") (pintype "bidirectional"))
    )
    (net (code "102") (name "unconnected-(JX1-BANK13_V7-Pad89)") (class "Default")
      (node (ref "JX1") (pin "89") (pinfunction "BANK13_V7_89") (pintype "bidirectional"))
    )
    (net (code "103") (name "unconnected-(JX1-BANK13_V8-Pad91)") (class "Default")
      (node (ref "JX1") (pin "91") (pinfunction "BANK13_V8_91") (pintype "bidirectional"))
    )
    (net (code "104") (name "unconnected-(JX1-BANK13_W8-Pad93)") (class "Default")
      (node (ref "JX1") (pin "93") (pinfunction "BANK13_W8_93") (pintype "bidirectional"))
    )
    (net (code "105") (name "unconnected-(JX1-BANK34_N18-Pad47)") (class "Default")
      (node (ref "JX1") (pin "47") (pinfunction "BANK34_N18_47") (pintype "bidirectional"))
    )
    (net (code "106") (name "unconnected-(JX1-BANK34_N20-Pad48)") (class "Default")
      (node (ref "JX1") (pin "48") (pinfunction "BANK34_N20_48") (pintype "bidirectional"))
    )
    (net (code "107") (name "unconnected-(JX1-BANK34_P19-Pad49)") (class "Default")
      (node (ref "JX1") (pin "49") (pinfunction "BANK34_P19_49") (pintype "bidirectional"))
    )
    (net (code "108") (name "unconnected-(JX1-BANK34_P20-Pad50)") (class "Default")
      (node (ref "JX1") (pin "50") (pinfunction "BANK34_P20_50") (pintype "bidirectional"))
    )
    (net (code "109") (name "unconnected-(JX1-BANK34_T16-Pad35)") (class "Default")
      (node (ref "JX1") (pin "35") (pinfunction "BANK34_T16_35") (pintype "bidirectional"))
    )
    (net (code "110") (name "unconnected-(JX1-BANK34_T20-Pad53)") (class "Default")
      (node (ref "JX1") (pin "53") (pinfunction "BANK34_T20_53") (pintype "bidirectional"))
    )
    (net (code "111") (name "unconnected-(JX1-BANK34_U14-Pad41)") (class "Default")
      (node (ref "JX1") (pin "41") (pinfunction "BANK34_U14_41") (pintype "bidirectional"))
    )
    (net (code "112") (name "unconnected-(JX1-BANK34_U15-Pad43)") (class "Default")
      (node (ref "JX1") (pin "43") (pinfunction "BANK34_U15_43") (pintype "bidirectional"))
    )
    (net (code "113") (name "unconnected-(JX1-BANK34_U17-Pad37)") (class "Default")
      (node (ref "JX1") (pin "37") (pinfunction "BANK34_U17_37") (pintype "bidirectional"))
    )
    (net (code "114") (name "unconnected-(JX1-BANK34_U18-Pad42)") (class "Default")
      (node (ref "JX1") (pin "42") (pinfunction "BANK34_U18_42") (pintype "bidirectional"))
    )
    (net (code "115") (name "unconnected-(JX1-BANK34_U19-Pad44)") (class "Default")
      (node (ref "JX1") (pin "44") (pinfunction "BANK34_U19_44") (pintype "bidirectional"))
    )
    (net (code "116") (name "unconnected-(JX1-BANK34_U20-Pad55)") (class "Default")
      (node (ref "JX1") (pin "55") (pinfunction "BANK34_U20_55") (pintype "bidirectional"))
    )
    (net (code "117") (name "unconnected-(JX1-BANK34_V15-Pad36)") (class "Default")
      (node (ref "JX1") (pin "36") (pinfunction "BANK34_V15_36") (pintype "bidirectional"))
    )
    (net (code "118") (name "unconnected-(JX1-BANK34_V20-Pad54)") (class "Default")
      (node (ref "JX1") (pin "54") (pinfunction "BANK34_V20_54") (pintype "bidirectional"))
    )
    (net (code "119") (name "unconnected-(JX1-BANK34_W15-Pad38)") (class "Default")
      (node (ref "JX1") (pin "38") (pinfunction "BANK34_W15_38") (pintype "bidirectional"))
    )
    (net (code "120") (name "unconnected-(JX1-BANK34_W20-Pad56)") (class "Default")
      (node (ref "JX1") (pin "56") (pinfunction "BANK34_W20_56") (pintype "bidirectional"))
    )
    (net (code "121") (name "unconnected-(JX1-BANK34_Y14-Pad32)") (class "Default")
      (node (ref "JX1") (pin "32") (pinfunction "BANK34_Y14_32") (pintype "bidirectional"))
    )
    (net (code "122") (name "unconnected-(JX1-BANK34_Y17-Pad31)") (class "Default")
      (node (ref "JX1") (pin "31") (pinfunction "BANK34_Y17_31") (pintype "bidirectional"))
    )
    (net (code "123") (name "unconnected-(JX1-CARRIER_SRST#-Pad6)") (class "Default")
      (node (ref "JX1") (pin "6") (pinfunction "CARRIER_SRST#_6") (pintype "bidirectional"))
    )
    (net (code "124") (name "unconnected-(JX1-FPGA_DONE-Pad8)") (class "Default")
      (node (ref "JX1") (pin "8") (pinfunction "FPGA_DONE_8") (pintype "bidirectional"))
    )
    (net (code "125") (name "unconnected-(JX1-FPGA_VBATT-Pad7)") (class "Default")
      (node (ref "JX1") (pin "7") (pinfunction "FPGA_VBATT_7") (pintype "bidirectional"))
    )
    (net (code "126") (name "unconnected-(JX1-GND-Pad85)") (class "Default")
      (node (ref "JX1") (pin "85") (pinfunction "GND_85") (pintype "bidirectional"))
    )
    (net (code "127") (name "unconnected-(JX1-PWR_EN-Pad5)") (class "Default")
      (node (ref "JX1") (pin "5") (pinfunction "PWR_EN_5") (pintype "bidirectional"))
    )
    (net (code "128") (name "unconnected-(JX2-BANK13_V5-Pad100)") (class "Default")
      (node (ref "JX2") (pin "100") (pinfunction "BANK13_V5_100") (pintype "bidirectional"))
    )
    (net (code "129") (name "unconnected-(JX2-BANK13_V6-Pad97)") (class "Default")
      (node (ref "JX2") (pin "97") (pinfunction "BANK13_V6_97") (pintype "bidirectional"))
    )
    (net (code "130") (name "unconnected-(JX2-BANK13_V10-Pad96)") (class "Default")
      (node (ref "JX2") (pin "96") (pinfunction "BANK13_V10_96") (pintype "bidirectional"))
    )
    (net (code "131") (name "unconnected-(JX2-BANK13_V11-Pad94)") (class "Default")
      (node (ref "JX2") (pin "94") (pinfunction "BANK13_V11_94") (pintype "bidirectional"))
    )
    (net (code "132") (name "unconnected-(JX2-BANK13_W6-Pad99)") (class "Default")
      (node (ref "JX2") (pin "99") (pinfunction "BANK13_W6_99") (pintype "bidirectional"))
    )
    (net (code "133") (name "unconnected-(JX2-BANK13_Y12-Pad93)") (class "Default")
      (node (ref "JX2") (pin "93") (pinfunction "BANK13_Y12_93") (pintype "bidirectional"))
    )
    (net (code "134") (name "unconnected-(JX2-BANK13_Y13-Pad95)") (class "Default")
      (node (ref "JX2") (pin "95") (pinfunction "BANK13_Y13_95") (pintype "bidirectional"))
    )
    (net (code "135") (name "unconnected-(JX2-BANK35_A20-Pad20)") (class "Default")
      (node (ref "JX2") (pin "20") (pinfunction "BANK35_A20_20") (pintype "bidirectional"))
    )
    (net (code "136") (name "unconnected-(JX2-BANK35_B19-Pad18)") (class "Default")
      (node (ref "JX2") (pin "18") (pinfunction "BANK35_B19_18") (pintype "bidirectional"))
    )
    (net (code "137") (name "unconnected-(JX2-BANK35_B20-Pad19)") (class "Default")
      (node (ref "JX2") (pin "19") (pinfunction "BANK35_B20_19") (pintype "bidirectional"))
    )
    (net (code "138") (name "unconnected-(JX2-BANK35_C20-Pad17)") (class "Default")
      (node (ref "JX2") (pin "17") (pinfunction "BANK35_C20_17") (pintype "bidirectional"))
    )
    (net (code "139") (name "unconnected-(JX2-BANK35_F19-Pad62)") (class "Default")
      (node (ref "JX2") (pin "62") (pinfunction "BANK35_F19_62") (pintype "bidirectional"))
    )
    (net (code "140") (name "unconnected-(JX2-BANK35_F20-Pad64)") (class "Default")
      (node (ref "JX2") (pin "64") (pinfunction "BANK35_F20_64") (pintype "bidirectional"))
    )
    (net (code "141") (name "unconnected-(JX2-BANK35_G14-Pad13)") (class "Default")
      (node (ref "JX2") (pin "13") (pinfunction "BANK35_G14_13") (pintype "bidirectional"))
    )
    (net (code "142") (name "unconnected-(JX2-BANK35_G17-Pad61)") (class "Default")
      (node (ref "JX2") (pin "61") (pinfunction "BANK35_G17_61") (pintype "bidirectional"))
    )
    (net (code "143") (name "unconnected-(JX2-BANK35_G18-Pad63)") (class "Default")
      (node (ref "JX2") (pin "63") (pinfunction "BANK35_G18_63") (pintype "bidirectional"))
    )
    (net (code "144") (name "unconnected-(JX2-BANK35_H16-Pad53)") (class "Default")
      (node (ref "JX2") (pin "53") (pinfunction "BANK35_H16_53") (pintype "bidirectional"))
    )
    (net (code "145") (name "unconnected-(JX2-BANK35_H17-Pad55)") (class "Default")
      (node (ref "JX2") (pin "55") (pinfunction "BANK35_H17_55") (pintype "bidirectional"))
    )
    (net (code "146") (name "unconnected-(JX2-BANK35_H18-Pad56)") (class "Default")
      (node (ref "JX2") (pin "56") (pinfunction "BANK35_H18_56") (pintype "bidirectional"))
    )
    (net (code "147") (name "unconnected-(JX2-BANK35_J15-Pad14)") (class "Default")
      (node (ref "JX2") (pin "14") (pinfunction "BANK35_J15_14") (pintype "bidirectional"))
    )
    (net (code "148") (name "unconnected-(JX2-BANK35_J18-Pad54)") (class "Default")
      (node (ref "JX2") (pin "54") (pinfunction "BANK35_J18_54") (pintype "bidirectional"))
    )
    (net (code "149") (name "unconnected-(JX2-BANK35_J19-Pad44)") (class "Default")
      (node (ref "JX2") (pin "44") (pinfunction "BANK35_J19_44") (pintype "bidirectional"))
    )
    (net (code "150") (name "unconnected-(JX2-BANK35_K17-Pad48)") (class "Default")
      (node (ref "JX2") (pin "48") (pinfunction "BANK35_K17_48") (pintype "bidirectional"))
    )
    (net (code "151") (name "unconnected-(JX2-BANK35_K18-Pad50)") (class "Default")
      (node (ref "JX2") (pin "50") (pinfunction "BANK35_K18_50") (pintype "bidirectional"))
    )
    (net (code "152") (name "unconnected-(JX2-BANK35_K19-Pad42)") (class "Default")
      (node (ref "JX2") (pin "42") (pinfunction "BANK35_K19_42") (pintype "bidirectional"))
    )
    (net (code "153") (name "unconnected-(JX2-BANK35_L16-Pad47)") (class "Default")
      (node (ref "JX2") (pin "47") (pinfunction "BANK35_L16_47") (pintype "bidirectional"))
    )
    (net (code "154") (name "unconnected-(JX2-BANK35_L17-Pad49)") (class "Default")
      (node (ref "JX2") (pin "49") (pinfunction "BANK35_L17_49") (pintype "bidirectional"))
    )
    (net (code "155") (name "unconnected-(JX2-BANK35_L20-Pad37)") (class "Default")
      (node (ref "JX2") (pin "37") (pinfunction "BANK35_L20_37") (pintype "bidirectional"))
    )
    (net (code "156") (name "unconnected-(JX2-BANK35_M17-Pad41)") (class "Default")
      (node (ref "JX2") (pin "41") (pinfunction "BANK35_M17_41") (pintype "bidirectional"))
    )
    (net (code "157") (name "unconnected-(JX2-BANK35_M18-Pad43)") (class "Default")
      (node (ref "JX2") (pin "43") (pinfunction "BANK35_M18_43") (pintype "bidirectional"))
    )
    (net (code "158") (name "unconnected-(JX2-BANK35_M20-Pad38)") (class "Default")
      (node (ref "JX2") (pin "38") (pinfunction "BANK35_M20_38") (pintype "bidirectional"))
    )
    (net (code "159") (name "unconnected-(JX2-BANK500_B5-Pad6)") (class "Default")
      (node (ref "JX2") (pin "6") (pinfunction "BANK500_B5_6") (pintype "bidirectional"))
    )
    (net (code "160") (name "unconnected-(JX2-BANK500_C5-Pad7)") (class "Default")
      (node (ref "JX2") (pin "7") (pinfunction "BANK500_C5_7") (pintype "bidirectional"))
    )
    (net (code "161") (name "unconnected-(JX2-BANK500_C6-Pad3)") (class "Default")
      (node (ref "JX2") (pin "3") (pinfunction "BANK500_C6_3") (pintype "bidirectional"))
    )
    (net (code "162") (name "unconnected-(JX2-BANK500_C8-Pad8)") (class "Default")
      (node (ref "JX2") (pin "8") (pinfunction "BANK500_C8_8") (pintype "bidirectional"))
    )
    (net (code "163") (name "unconnected-(JX2-BANK500_D9-Pad4)") (class "Default")
      (node (ref "JX2") (pin "4") (pinfunction "BANK500_D9_4") (pintype "bidirectional"))
    )
    (net (code "164") (name "unconnected-(JX2-BANK500_E6-Pad5)") (class "Default")
      (node (ref "JX2") (pin "5") (pinfunction "BANK500_E6_5") (pintype "bidirectional"))
    )
    (net (code "165") (name "unconnected-(JX2-BANK500_E8-Pad1)") (class "Default")
      (node (ref "JX2") (pin "1") (pinfunction "BANK500_E8_1") (pintype "bidirectional"))
    )
    (net (code "166") (name "unconnected-(JX2-BANK500_E9-Pad2)") (class "Default")
      (node (ref "JX2") (pin "2") (pinfunction "BANK500_E9_2") (pintype "bidirectional"))
    )
    (net (code "167") (name "unconnected-(JX2-INIT#-Pad9)") (class "Default")
      (node (ref "JX2") (pin "9") (pinfunction "INIT#_9") (pintype "bidirectional"))
    )
    (net (code "168") (name "unconnected-(TCXO-NC-Pad10)") (class "Default")
      (node (ref "TCXO") (pin "10") (pinfunction "NC_10") (pintype "no_connect"))
    )
    (net (code "169") (name "unconnected-(TCXO-NC_2-Pad2)") (class "Default")
      (node (ref "TCXO") (pin "2") (pinfunction "NC_2_2") (pintype "no_connect"))
    )
    (net (code "170") (name "unconnected-(TCXO-NC_3-Pad3)") (class "Default")
      (node (ref "TCXO") (pin "3") (pinfunction "NC_3_3") (pintype "no_connect"))
    )
    (net (code "171") (name "unconnected-(TCXO-NC_4-Pad5)") (class "Default")
      (node (ref "TCXO") (pin "5") (pinfunction "NC_4_5") (pintype "no_connect"))
    )
    (net (code "172") (name "unconnected-(TCXO-NC_5-Pad7)") (class "Default")
      (node (ref "TCXO") (pin "7") (pinfunction "NC_5_7") (pintype "no_connect"))
    )
    (net (code "173") (name "unconnected-(TCXO-NC_6-Pad8)") (class "Default")
      (node (ref "TCXO") (pin "8") (pinfunction "NC_6_8") (pintype "no_connect"))
    )
  )
)
